# rampshh.net
KiCad netlist of a schematic drawn in Altium Designer
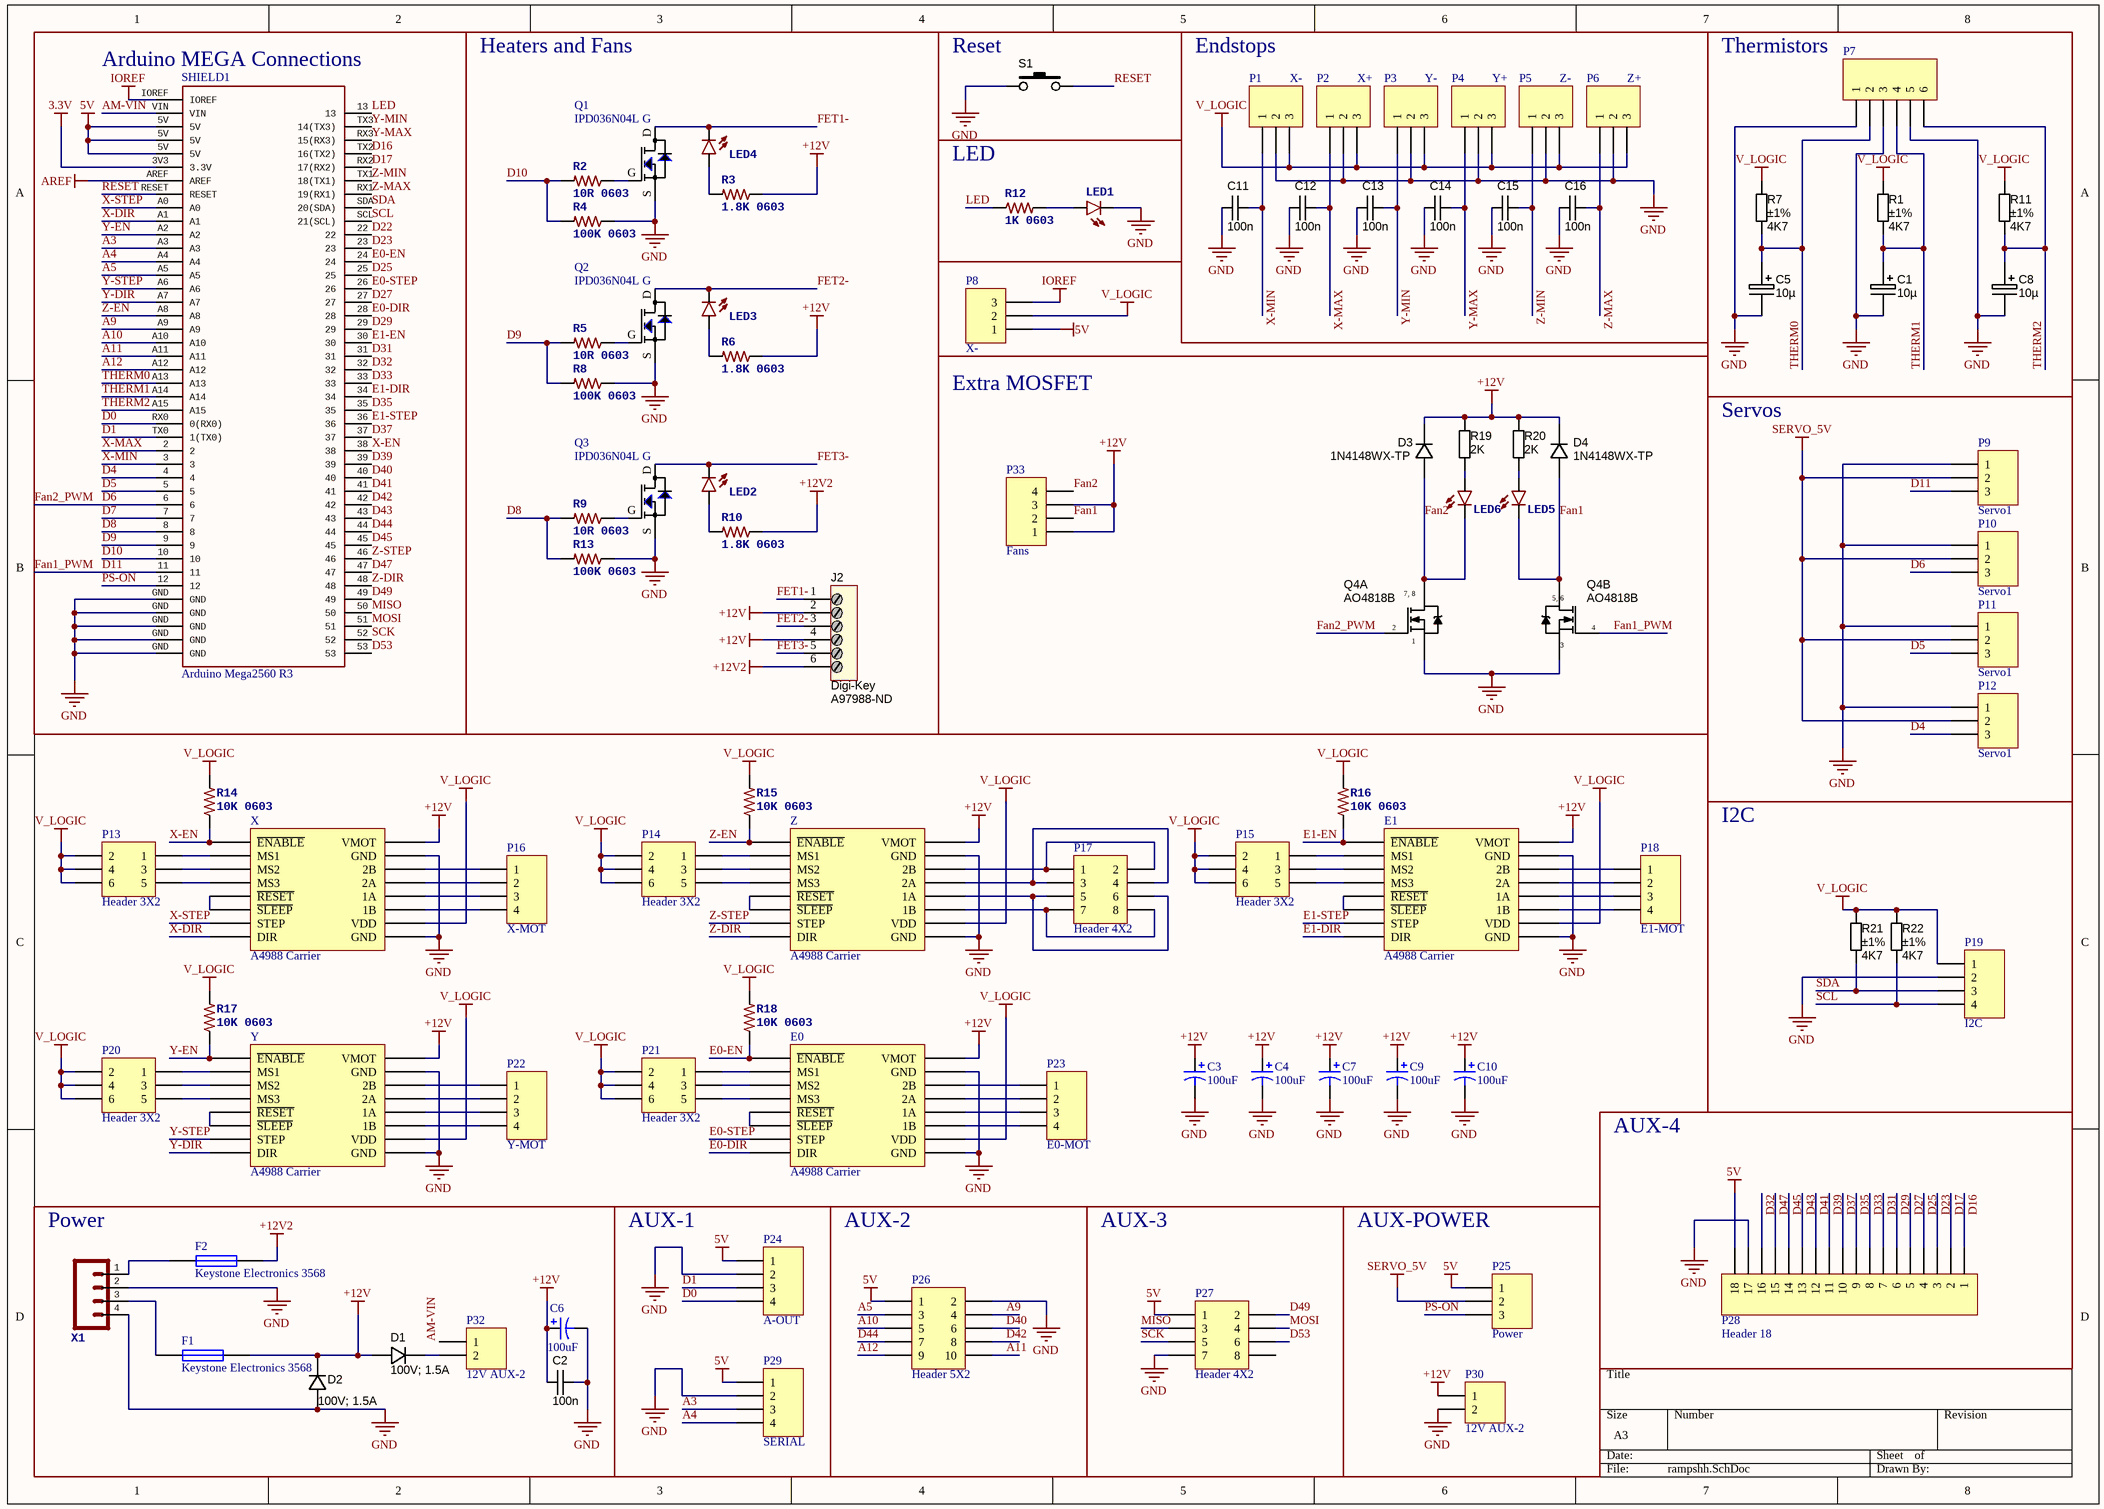
[diagram p0: rampshh.SchDoc]

(export (version "E")
  (design (tool "Eeschema 10.0.6"))
  (components
    (comp (ref "C1")
      (value "10µ")
      (footprint "153CLV-0405")
      (description "Capacitor SMD Electrolytic 10uF 20% 100V Radial")
      (fields (field (name "TOLERANCE") "±20%") (field (name "MANUFACTURER") "Panasonic - ECG"))
      (libsource (lib "PBL - Capacitors") (part "CAPE_10u_100V_SMD"))
    )
    (comp (ref "C2")
      (value "100n")
      (footprint "CAPC2012X135N")
      (description "Capacitor SMD Cer 100nF 10% 50V X7R 0805")
      (fields (field (name "TOLERANCE") "±10%") (field (name "Comment") "approved sub OK"))
      (libsource (lib "PBL - Capacitors") (part "CAPC_100n_0805_X7R_50V_10%"))
    )
    (comp (ref "C3")
      (value "100uF")
      (footprint "Kemet EDK107M035A9HAA")
      (description "Polarized Capacitor (Radial)")
      (fields (field (name "PUBLISHER") "Altium Limited"))
      (libsource (lib "Miscellaneous Devices") (part "Cap Pol1"))
    )
    (comp (ref "C4")
      (value "100uF")
      (footprint "Kemet EDK107M035A9HAA")
      (description "Polarized Capacitor (Radial)")
      (fields (field (name "PUBLISHER") "Altium Limited"))
      (libsource (lib "Miscellaneous Devices") (part "Cap Pol1"))
    )
    (comp (ref "C5")
      (value "10µ")
      (footprint "153CLV-0405")
      (description "Capacitor SMD Electrolytic 10uF 20% 100V Radial")
      (fields (field (name "TOLERANCE") "±20%") (field (name "MANUFACTURER") "Panasonic - ECG"))
      (libsource (lib "PBL - Capacitors") (part "CAPE_10u_100V_SMD"))
    )
    (comp (ref "C6")
      (value "100uF")
      (footprint "Kemet EDK107M035A9HAA")
      (description "Polarized Capacitor (Radial)")
      (fields (field (name "PUBLISHER") "Altium Limited"))
      (libsource (lib "Miscellaneous Devices") (part "Cap Pol1"))
    )
    (comp (ref "C7")
      (value "100uF")
      (footprint "Kemet EDK107M035A9HAA")
      (description "Polarized Capacitor (Radial)")
      (fields (field (name "PUBLISHER") "Altium Limited"))
      (libsource (lib "Miscellaneous Devices") (part "Cap Pol1"))
    )
    (comp (ref "C8")
      (value "10µ")
      (footprint "153CLV-0405")
      (description "Capacitor SMD Electrolytic 10uF 20% 100V Radial")
      (fields (field (name "TOLERANCE") "±20%") (field (name "MANUFACTURER") "Panasonic - ECG"))
      (libsource (lib "PBL - Capacitors") (part "CAPE_10u_100V_SMD"))
    )
    (comp (ref "C9")
      (value "100uF")
      (footprint "Kemet EDK107M035A9HAA")
      (description "Polarized Capacitor (Radial)")
      (fields (field (name "PUBLISHER") "Altium Limited"))
      (libsource (lib "Miscellaneous Devices") (part "Cap Pol1"))
    )
    (comp (ref "C10")
      (value "100uF")
      (footprint "Kemet EDK107M035A9HAA")
      (description "Polarized Capacitor (Radial)")
      (fields (field (name "PUBLISHER") "Altium Limited"))
      (libsource (lib "Miscellaneous Devices") (part "Cap Pol1"))
    )
    (comp (ref "C11")
      (value "100n")
      (footprint "CAPC1608X90N")
      (description "Capacitor SMD Cer 100nF 10% 50V X7R 0603")
      (fields (field (name "TOLERANCE") "±10%") (field (name "Comment") "approved sub OK"))
      (libsource (lib "PBL - Capacitors") (part "CAPC_100n_0603_X7R_50V_10%"))
    )
    (comp (ref "C12")
      (value "100n")
      (footprint "CAPC1608X90N")
      (description "Capacitor SMD Cer 100nF 10% 50V X7R 0603")
      (fields (field (name "TOLERANCE") "±10%") (field (name "Comment") "approved sub OK"))
      (libsource (lib "PBL - Capacitors") (part "CAPC_100n_0603_X7R_50V_10%"))
    )
    (comp (ref "C13")
      (value "100n")
      (footprint "CAPC1608X90N")
      (description "Capacitor SMD Cer 100nF 10% 50V X7R 0603")
      (fields (field (name "TOLERANCE") "±10%") (field (name "Comment") "approved sub OK"))
      (libsource (lib "PBL - Capacitors") (part "CAPC_100n_0603_X7R_50V_10%"))
    )
    (comp (ref "C14")
      (value "100n")
      (footprint "CAPC1608X90N")
      (description "Capacitor SMD Cer 100nF 10% 50V X7R 0603")
      (fields (field (name "TOLERANCE") "±10%") (field (name "Comment") "approved sub OK"))
      (libsource (lib "PBL - Capacitors") (part "CAPC_100n_0603_X7R_50V_10%"))
    )
    (comp (ref "C15")
      (value "100n")
      (footprint "CAPC1608X90N")
      (description "Capacitor SMD Cer 100nF 10% 50V X7R 0603")
      (fields (field (name "TOLERANCE") "±10%") (field (name "Comment") "approved sub OK"))
      (libsource (lib "PBL - Capacitors") (part "CAPC_100n_0603_X7R_50V_10%"))
    )
    (comp (ref "C16")
      (value "100n")
      (footprint "CAPC1608X90N")
      (description "Capacitor SMD Cer 100nF 10% 50V X7R 0603")
      (fields (field (name "TOLERANCE") "±10%") (field (name "Comment") "approved sub OK"))
      (libsource (lib "PBL - Capacitors") (part "CAPC_100n_0603_X7R_50V_10%"))
    )
    (comp (ref "D1")
      (value "100V; 1.5A")
      (footprint "DO-214AC")
      (description "Diode SMD 100V 1.5A SMA")
      (libsource (lib "PBL - Diodes") (part "DIODE_100V_1.5A_SMA"))
    )
    (comp (ref "D2")
      (value "100V; 1.5A")
      (footprint "DO-214AC")
      (description "Diode SMD 100V 1.5A SMA")
      (libsource (lib "PBL - Diodes") (part "DIODE_100V_1.5A_SMA"))
    )
    (comp (ref "D3")
      (value "DIODE_75V_500mW")
      (footprint "SOD323")
      (description "Diode SMD 300mA 0.5W SOD323")
      (fields
        (field (name "MANUFACTURER") "Micro Commercial Co")
        (field (name "MANUFACTURER PART NUMBER") "1N4148WX-TP")
      )
      (libsource (lib "PBL - Diodes") (part "DIODE_75V_500mW"))
    )
    (comp (ref "D4")
      (value "DIODE_75V_500mW")
      (footprint "SOD323")
      (description "Diode SMD 300mA 0.5W SOD323")
      (fields
        (field (name "MANUFACTURER") "Micro Commercial Co")
        (field (name "MANUFACTURER PART NUMBER") "1N4148WX-TP")
      )
      (libsource (lib "PBL - Diodes") (part "DIODE_75V_500mW"))
    )
    (comp (ref "E0")
      (value "A4988 Carrier")
      (footprint "A4988 Carrier")
      (libsource (lib "Schlib1") (part "A4988 Carrier"))
    )
    (comp (ref "E1")
      (value "A4988 Carrier")
      (footprint "A4988 Carrier")
      (libsource (lib "Schlib1") (part "A4988 Carrier"))
    )
    (comp (ref "F1")
      (value "Keystone Electronics 3568")
      (footprint "Keystone Electronics 3568 Fuse Holder")
      (description "Fuse")
      (fields (field (name "PUBLISHER") "Altium Limited"))
      (libsource (lib "Miscellaneous Devices") (part "Fuse 1"))
    )
    (comp (ref "F2")
      (value "Keystone Electronics 3568")
      (footprint "Keystone Electronics 3568 Fuse Holder")
      (description "Fuse")
      (fields (field (name "PUBLISHER") "Altium Limited"))
      (libsource (lib "Miscellaneous Devices") (part "Fuse 1"))
    )
    (comp (ref "J2")
      (value "6P_ScrewTerm_90S")
      (footprint "6P_PCB_ScrewTerm90S")
      (description "TERM BLOCK 6POS SIDE ENT STACKABLE 5.08MM")
      (fields
        (field (name "VOLTAGE") "300V")
        (field (name "SUPPLIER 1") "Digi-Key")
        (field (name "SUPPLIER PART NUMBER 1") "A97988-ND")
      )
      (libsource (lib "PBL - Connectors") (part "6P_ScrewTerm_90S"))
    )
    (comp (ref "LED1")
      (value "Blue LEDs for production use    Various blue LEDs stocked by SparkFun production 0603 - DIO-08575 Rebel - DIO-09553 1206 - DIO-09911")
      (footprint "LED-0603")
      (libsource (lib "SparkFun-LED") (part "LED-BLUE0603"))
    )
    (comp (ref "LED2")
      (value "Blue LEDs for production use    Various blue LEDs stocked by SparkFun production 0603 - DIO-08575 Rebel - DIO-09553 1206 - DIO-09911")
      (footprint "LED-0603")
      (libsource (lib "SparkFun-LED") (part "LED-BLUE0603"))
    )
    (comp (ref "LED3")
      (value "Blue LEDs for production use    Various blue LEDs stocked by SparkFun production 0603 - DIO-08575 Rebel - DIO-09553 1206 - DIO-09911")
      (footprint "LED-0603")
      (libsource (lib "SparkFun-LED") (part "LED-BLUE0603"))
    )
    (comp (ref "LED4")
      (value "Blue LEDs for production use    Various blue LEDs stocked by SparkFun production 0603 - DIO-08575 Rebel - DIO-09553 1206 - DIO-09911")
      (footprint "LED-0603")
      (libsource (lib "SparkFun-LED") (part "LED-BLUE0603"))
    )
    (comp (ref "LED5")
      (value "Blue LEDs for production use    Various blue LEDs stocked by SparkFun production 0603 - DIO-08575 Rebel - DIO-09553 1206 - DIO-09911")
      (footprint "LED-0603")
      (libsource (lib "SparkFun-LED") (part "LED-BLUE0603"))
    )
    (comp (ref "LED6")
      (value "Blue LEDs for production use    Various blue LEDs stocked by SparkFun production 0603 - DIO-08575 Rebel - DIO-09553 1206 - DIO-09911")
      (footprint "LED-0603")
      (libsource (lib "SparkFun-LED") (part "LED-BLUE0603"))
    )
    (comp (ref "P1")
      (value "X-")
      (footprint "Header 3x1 Male")
      (description "Header, 3-Pin")
      (fields (field (name "PUBLISHER") "Altium Limited"))
      (libsource (lib "Miscellaneous Connectors") (part "Header 3"))
    )
    (comp (ref "P2")
      (value "X+")
      (footprint "Header 3x1 Male")
      (description "Header, 3-Pin")
      (fields (field (name "PUBLISHER") "Altium Limited"))
      (libsource (lib "Miscellaneous Connectors") (part "Header 3"))
    )
    (comp (ref "P3")
      (value "Y-")
      (footprint "Header 3x1 Male")
      (description "Header, 3-Pin")
      (fields (field (name "PUBLISHER") "Altium Limited"))
      (libsource (lib "Miscellaneous Connectors") (part "Header 3"))
    )
    (comp (ref "P4")
      (value "Y+")
      (footprint "Header 3x1 Male")
      (description "Header, 3-Pin")
      (fields (field (name "PUBLISHER") "Altium Limited"))
      (libsource (lib "Miscellaneous Connectors") (part "Header 3"))
    )
    (comp (ref "P5")
      (value "Z-")
      (footprint "Header 3x1 Male")
      (description "Header, 3-Pin")
      (fields (field (name "PUBLISHER") "Altium Limited"))
      (libsource (lib "Miscellaneous Connectors") (part "Header 3"))
    )
    (comp (ref "P6")
      (value "Z+")
      (footprint "Header 3x1 Male")
      (description "Header, 3-Pin")
      (fields (field (name "PUBLISHER") "Altium Limited"))
      (libsource (lib "Miscellaneous Connectors") (part "Header 3"))
    )
    (comp (ref "P7")
      (value "Header 6")
      (footprint "HDR1X6")
      (description "Header, 6-Pin")
      (fields (field (name "PUBLISHER") "Altium Limited"))
      (libsource (lib "Miscellaneous Connectors") (part "Header 6"))
    )
    (comp (ref "P8")
      (value "X-")
      (footprint "Header 3x1 Male")
      (description "Header, 3-Pin")
      (fields (field (name "PUBLISHER") "Altium Limited"))
      (libsource (lib "") (part "Header 3_2"))
    )
    (comp (ref "P9")
      (value "Servo1")
      (footprint "Header 3x1 Male")
      (description "Header, 3-Pin")
      (fields (field (name "PUBLISHER") "Altium Limited"))
      (libsource (lib "") (part "Header 3_1"))
    )
    (comp (ref "P10")
      (value "Servo1")
      (footprint "Header 3x1 Male")
      (description "Header, 3-Pin")
      (fields (field (name "PUBLISHER") "Altium Limited"))
      (libsource (lib "") (part "Header 3_1"))
    )
    (comp (ref "P11")
      (value "Servo1")
      (footprint "Header 3x1 Male")
      (description "Header, 3-Pin")
      (fields (field (name "PUBLISHER") "Altium Limited"))
      (libsource (lib "") (part "Header 3_1"))
    )
    (comp (ref "P12")
      (value "Servo1")
      (footprint "Header 3x1 Male")
      (description "Header, 3-Pin")
      (fields (field (name "PUBLISHER") "Altium Limited"))
      (libsource (lib "") (part "Header 3_1"))
    )
    (comp (ref "P13")
      (value "Header 3X2")
      (footprint "Header 3x2 Male")
      (description "Header, 3-Pin, Dual row")
      (fields (field (name "PUBLISHER") "Altium Limited"))
      (libsource (lib "Miscellaneous Connectors") (part "Header 3X2"))
    )
    (comp (ref "P14")
      (value "Header 3X2")
      (footprint "Header 3x2 Male")
      (description "Header, 3-Pin, Dual row")
      (fields (field (name "PUBLISHER") "Altium Limited"))
      (libsource (lib "Miscellaneous Connectors") (part "Header 3X2"))
    )
    (comp (ref "P15")
      (value "Header 3X2")
      (footprint "Header 3x2 Male")
      (description "Header, 3-Pin, Dual row")
      (fields (field (name "PUBLISHER") "Altium Limited"))
      (libsource (lib "Miscellaneous Connectors") (part "Header 3X2"))
    )
    (comp (ref "P16")
      (value "X-MOT")
      (footprint "Header 4x1 Male")
      (description "Header, 4-Pin")
      (fields (field (name "PUBLISHER") "Altium Limited"))
      (libsource (lib "Miscellaneous Connectors") (part "Header 4"))
    )
    (comp (ref "P17")
      (value "Header 4X2")
      (footprint "Header 4x2 Male")
      (description "Header, 4-Pin, Dual row")
      (fields (field (name "PUBLISHER") "Altium Limited"))
      (libsource (lib "Miscellaneous Connectors") (part "Header 4X2"))
    )
    (comp (ref "P18")
      (value "E1-MOT")
      (footprint "Header 4x1 Male")
      (description "Header, 4-Pin")
      (fields (field (name "PUBLISHER") "Altium Limited"))
      (libsource (lib "Miscellaneous Connectors") (part "Header 4"))
    )
    (comp (ref "P19")
      (value "I2C")
      (footprint "Header 4x1 Male")
      (description "Header, 4-Pin")
      (fields (field (name "PUBLISHER") "Altium Limited"))
      (libsource (lib "Miscellaneous Connectors") (part "Header 4"))
    )
    (comp (ref "P20")
      (value "Header 3X2")
      (footprint "Header 3x2 Male")
      (description "Header, 3-Pin, Dual row")
      (fields (field (name "PUBLISHER") "Altium Limited"))
      (libsource (lib "Miscellaneous Connectors") (part "Header 3X2"))
    )
    (comp (ref "P21")
      (value "Header 3X2")
      (footprint "Header 3x2 Male")
      (description "Header, 3-Pin, Dual row")
      (fields (field (name "PUBLISHER") "Altium Limited"))
      (libsource (lib "Miscellaneous Connectors") (part "Header 3X2"))
    )
    (comp (ref "P22")
      (value "Y-MOT")
      (footprint "Header 4x1 Male")
      (description "Header, 4-Pin")
      (fields (field (name "PUBLISHER") "Altium Limited"))
      (libsource (lib "Miscellaneous Connectors") (part "Header 4"))
    )
    (comp (ref "P23")
      (value "E0-MOT")
      (footprint "Header 4x1 Male")
      (description "Header, 4-Pin")
      (fields (field (name "PUBLISHER") "Altium Limited"))
      (libsource (lib "Miscellaneous Connectors") (part "Header 4"))
    )
    (comp (ref "P24")
      (value "A-OUT")
      (footprint "Header 4x1 Male")
      (description "Header, 4-Pin")
      (fields (field (name "PUBLISHER") "Altium Limited"))
      (libsource (lib "Miscellaneous Connectors") (part "Header 4"))
    )
    (comp (ref "P25")
      (value "Power")
      (footprint "Header 3x1 Male")
      (description "Header, 3-Pin")
      (fields (field (name "PUBLISHER") "Altium Limited"))
      (libsource (lib "") (part "Header 3_1"))
    )
    (comp (ref "P26")
      (value "Header 5X2")
      (footprint "Header 5x2 Male")
      (description "Header, 5-Pin, Dual row")
      (fields (field (name "PUBLISHER") "Altium Limited"))
      (libsource (lib "Miscellaneous Connectors") (part "Header 5X2"))
    )
    (comp (ref "P27")
      (value "Header 4X2")
      (footprint "Header 4x2 Male")
      (description "Header, 4-Pin, Dual row")
      (fields (field (name "PUBLISHER") "Altium Limited"))
      (libsource (lib "Miscellaneous Connectors") (part "Header 4X2"))
    )
    (comp (ref "P28")
      (value "Header 18")
      (footprint "HDR1X18")
      (description "Header, 18-Pin")
      (fields (field (name "PUBLISHER") "Altium Limited"))
      (libsource (lib "Miscellaneous Connectors") (part "Header 18"))
    )
    (comp (ref "P29")
      (value "SERIAL")
      (footprint "Header 4x1 Male")
      (description "Header, 4-Pin")
      (fields (field (name "PUBLISHER") "Altium Limited"))
      (libsource (lib "Miscellaneous Connectors") (part "Header 4"))
    )
    (comp (ref "P30")
      (value "12V AUX-2")
      (footprint "Header 2x1 Male")
      (description "Header, 2-Pin")
      (fields (field (name "PUBLISHER") "Altium Limited"))
      (libsource (lib "Miscellaneous Connectors") (part "Header 2"))
    )
    (comp (ref "P32")
      (value "12V AUX-2")
      (footprint "Header 2x1 Male")
      (description "Header, 2-Pin")
      (fields (field (name "PUBLISHER") "Altium Limited"))
      (libsource (lib "Miscellaneous Connectors") (part "Header 2"))
    )
    (comp (ref "P33")
      (value "Fans")
      (footprint "Header 4x1 Male")
      (description "Header, 4-Pin")
      (fields (field (name "PUBLISHER") "Altium Limited"))
      (libsource (lib "") (part "Header 4_1"))
    )
    (comp (ref "Q1")
      (value "IPD036N04L G")
      (footprint "IPD036N04L G")
      (libsource (lib "Schlib1") (part "IPD036N04L G"))
    )
    (comp (ref "Q2")
      (value "IPD036N04L G")
      (footprint "IPD036N04L G")
      (libsource (lib "Schlib1") (part "IPD036N04L G"))
    )
    (comp (ref "Q3")
      (value "IPD036N04L G")
      (footprint "IPD036N04L G")
      (libsource (lib "Schlib1") (part "IPD036N04L G"))
    )
    (comp (ref "Q4")
      (value "MOSFET_AO4818B")
      (footprint "SOIC127P600X175-8AN")
      (description "MOSFET Dual-Channel 30V 8.5A SOIC-8 SMD")
      (fields (field (name "MANUFACTURER PART NUMBER 1") "AO4818B"))
      (libsource (lib "PBL - Transistors") (part "MOSFET_AO4818B"))
    )
    (comp (ref "R1")
      (value "4K7")
      (footprint "RESC2012X70N")
      (description "Resistor SMD chip 4.7k Ohm 0.125W 1% 0805")
      (fields (field (name "TOLERANCE") "±1%") (field (name "Comment") "Thick Film"))
      (libsource (lib "PBL - Resistors") (part "RES_4K7_0805_1%"))
    )
    (comp (ref "R2")
      (value "10R 0603")
      (footprint "RESC1608X55N")
      (libsource (lib "SparkFun-Resistors") (part "1KOHM-1/10W-1%(0603)"))
    )
    (comp (ref "R3")
      (value "1.8K 0603")
      (footprint "0603-RES")
      (libsource (lib "SparkFun-Resistors") (part "1KOHM-1/10W-1%(0603)"))
    )
    (comp (ref "R4")
      (value "100K 0603")
      (footprint "RESC1608X55N")
      (libsource (lib "SparkFun-Resistors") (part "1KOHM-1/10W-1%(0603)"))
    )
    (comp (ref "R5")
      (value "10R 0603")
      (footprint "RESC1608X55N")
      (libsource (lib "SparkFun-Resistors") (part "1KOHM-1/10W-1%(0603)"))
    )
    (comp (ref "R6")
      (value "1.8K 0603")
      (footprint "0603-RES")
      (libsource (lib "SparkFun-Resistors") (part "1KOHM-1/10W-1%(0603)"))
    )
    (comp (ref "R7")
      (value "4K7")
      (footprint "RESC2012X70N")
      (description "Resistor SMD chip 4.7k Ohm 0.125W 1% 0805")
      (fields (field (name "TOLERANCE") "±1%") (field (name "Comment") "Thick Film"))
      (libsource (lib "PBL - Resistors") (part "RES_4K7_0805_1%"))
    )
    (comp (ref "R8")
      (value "100K 0603")
      (footprint "RESC1608X55N")
      (libsource (lib "SparkFun-Resistors") (part "1KOHM-1/10W-1%(0603)"))
    )
    (comp (ref "R9")
      (value "10R 0603")
      (footprint "RESC1608X55N")
      (libsource (lib "SparkFun-Resistors") (part "1KOHM-1/10W-1%(0603)"))
    )
    (comp (ref "R10")
      (value "1.8K 0603")
      (footprint "0603-RES")
      (libsource (lib "SparkFun-Resistors") (part "1KOHM-1/10W-1%(0603)"))
    )
    (comp (ref "R11")
      (value "4K7")
      (footprint "RESC2012X70N")
      (description "Resistor SMD chip 4.7k Ohm 0.125W 1% 0805")
      (fields (field (name "TOLERANCE") "±1%") (field (name "Comment") "Thick Film"))
      (libsource (lib "PBL - Resistors") (part "RES_4K7_0805_1%"))
    )
    (comp (ref "R12")
      (value "1K 0603")
      (footprint "0603-RES")
      (libsource (lib "SparkFun-Resistors") (part "1KOHM-1/10W-1%(0603)"))
    )
    (comp (ref "R13")
      (value "100K 0603")
      (footprint "RESC1608X55N")
      (libsource (lib "SparkFun-Resistors") (part "1KOHM-1/10W-1%(0603)"))
    )
    (comp (ref "R14")
      (value "10K 0603")
      (footprint "0603-RES")
      (libsource (lib "SparkFun-Resistors") (part "1KOHM-1/10W-1%(0603)"))
    )
    (comp (ref "R15")
      (value "10K 0603")
      (footprint "0603-RES")
      (libsource (lib "SparkFun-Resistors") (part "1KOHM-1/10W-1%(0603)"))
    )
    (comp (ref "R16")
      (value "10K 0603")
      (footprint "0603-RES")
      (libsource (lib "SparkFun-Resistors") (part "1KOHM-1/10W-1%(0603)"))
    )
    (comp (ref "R17")
      (value "10K 0603")
      (footprint "0603-RES")
      (libsource (lib "SparkFun-Resistors") (part "1KOHM-1/10W-1%(0603)"))
    )
    (comp (ref "R18")
      (value "10K 0603")
      (footprint "0603-RES")
      (libsource (lib "SparkFun-Resistors") (part "1KOHM-1/10W-1%(0603)"))
    )
    (comp (ref "R19")
      (value "2K")
      (footprint "RESC1608X55N")
      (description "Resistor SMD chip 330 Ohm 0.1W 5% 0603")
      (fields (field (name "TOLERANCE") "±5%") (field (name "Comment") "Thick Film"))
      (libsource (lib "PBL - Resistors") (part "RES_330R_0603_5%"))
    )
    (comp (ref "R20")
      (value "2K")
      (footprint "RESC1608X55N")
      (description "Resistor SMD chip 330 Ohm 0.1W 5% 0603")
      (fields (field (name "TOLERANCE") "±5%") (field (name "Comment") "Thick Film"))
      (libsource (lib "PBL - Resistors") (part "RES_330R_0603_5%"))
    )
    (comp (ref "R21")
      (value "4K7")
      (footprint "RESC2012X70N")
      (description "Resistor SMD chip 4.7k Ohm 0.125W 1% 0805")
      (fields (field (name "TOLERANCE") "±1%") (field (name "Comment") "Thick Film"))
      (libsource (lib "PBL - Resistors") (part "RES_4K7_0805_1%"))
    )
    (comp (ref "R22")
      (value "4K7")
      (footprint "RESC2012X70N")
      (description "Resistor SMD chip 4.7k Ohm 0.125W 1% 0805")
      (fields (field (name "TOLERANCE") "±1%") (field (name "Comment") "Thick Film"))
      (libsource (lib "PBL - Resistors") (part "RES_4K7_0805_1%"))
    )
    (comp (ref "S1")
      (value "SW_THT_PB_4.3mm")
      (footprint "FSMRACD")
      (description "Switch, tact, 4.3mm stem")
      (libsource (lib "PBL - Switches") (part "SW_THT_PB_4.3mm"))
    )
    (comp (ref "SHIELD1")
      (value "Arduino Mega2560 R3")
      (footprint "Arduino Mega Shield - No Text")
      (libsource (lib "Schlib1") (part "Arduino Mega2560 R3"))
    )
    (comp (ref "X")
      (value "A4988 Carrier")
      (footprint "A4988 Carrier")
      (libsource (lib "Schlib1") (part "A4988 Carrier"))
    )
    (comp (ref "X1")
      (value "Header 4Standard 4-pin 0.1\" header. Use with straight break away headers (SKU : PRT-00116), right angle break away headers (PRT-00553), swiss pins (PRT-00743), machine pins (PRT-00117), and female headers (PRT-00115). Molex polarized connector foot print use with SKU : PRT-08231 with associated crimp pins and housings. 1MM SMD Version SKU: PRT-10208")
      (footprint "MSTBA4")
      (libsource (lib "SparkFun-Connectors") (part "M04SCREW"))
    )
    (comp (ref "Y")
      (value "A4988 Carrier")
      (footprint "A4988 Carrier")
      (libsource (lib "Schlib1") (part "A4988 Carrier"))
    )
    (comp (ref "Z")
      (value "A4988 Carrier")
      (footprint "A4988 Carrier")
      (libsource (lib "Schlib1") (part "A4988 Carrier"))
    )
  )
  (nets
    (net (code "1") (name "+12V") (class "Default")
      (node (ref "C10") (pin "1") (pinfunction "1_1") (pintype "passive"))
      (node (ref "C2") (pin "1") (pintype "passive"))
      (node (ref "C3") (pin "1") (pinfunction "1_1") (pintype "passive"))
      (node (ref "C4") (pin "1") (pinfunction "1_1") (pintype "passive"))
      (node (ref "C6") (pin "1") (pinfunction "1_1") (pintype "passive"))
      (node (ref "C7") (pin "1") (pinfunction "1_1") (pintype "passive"))
      (node (ref "C9") (pin "1") (pinfunction "1_1") (pintype "passive"))
      (node (ref "D1") (pin "A") (pinfunction "A_A") (pintype "passive"))
      (node (ref "D2") (pin "K") (pinfunction "K_K") (pintype "passive"))
      (node (ref "D3") (pin "K") (pinfunction "K_K") (pintype "passive"))
      (node (ref "D4") (pin "K") (pinfunction "K_K") (pintype "passive"))
      (node (ref "E0") (pin "VMOT") (pinfunction "VMOT_VMOT") (pintype "passive"))
      (node (ref "E1") (pin "VMOT") (pinfunction "VMOT_VMOT") (pintype "passive"))
      (node (ref "F1") (pin "2") (pinfunction "2_2") (pintype "passive"))
      (node (ref "J2") (pin "2") (pinfunction "2_2") (pintype "passive"))
      (node (ref "J2") (pin "4") (pinfunction "4_4") (pintype "passive"))
      (node (ref "P30") (pin "1") (pinfunction "1_1") (pintype "passive"))
      (node (ref "P33") (pin "1") (pinfunction "1_1") (pintype "passive"))
      (node (ref "P33") (pin "3") (pinfunction "3_3") (pintype "passive"))
      (node (ref "R19") (pin "1") (pinfunction "1_1") (pintype "passive"))
      (node (ref "R20") (pin "1") (pinfunction "1_1") (pintype "passive"))
      (node (ref "R3") (pin "1") (pinfunction "1_1") (pintype "passive"))
      (node (ref "R6") (pin "1") (pinfunction "1_1") (pintype "passive"))
      (node (ref "X") (pin "VMOT") (pinfunction "VMOT_VMOT") (pintype "passive"))
      (node (ref "Y") (pin "VMOT") (pinfunction "VMOT_VMOT") (pintype "passive"))
      (node (ref "Z") (pin "VMOT") (pinfunction "VMOT_VMOT") (pintype "passive"))
    )
    (net (code "2") (name "+12V2") (class "Default")
      (node (ref "F2") (pin "2") (pinfunction "2_2") (pintype "passive"))
      (node (ref "J2") (pin "6") (pinfunction "6_6") (pintype "passive"))
      (node (ref "R10") (pin "1") (pinfunction "1_1") (pintype "passive"))
    )
    (net (code "3") (name "/A3") (class "Default")
      (node (ref "P29") (pin "3") (pinfunction "3_3") (pintype "passive"))
      (node (ref "SHIELD1") (pin "A3") (pinfunction "A3_A3") (pintype "passive"))
    )
    (net (code "4") (name "/A4") (class "Default")
      (node (ref "P29") (pin "4") (pinfunction "4_4") (pintype "passive"))
      (node (ref "SHIELD1") (pin "A4") (pinfunction "A4_A4") (pintype "passive"))
    )
    (net (code "5") (name "/A5") (class "Default")
      (node (ref "P26") (pin "3") (pinfunction "3_3") (pintype "passive"))
      (node (ref "SHIELD1") (pin "A5") (pinfunction "A5_A5") (pintype "passive"))
    )
    (net (code "6") (name "/A9") (class "Default")
      (node (ref "P26") (pin "4") (pinfunction "4_4") (pintype "passive"))
      (node (ref "SHIELD1") (pin "A9") (pinfunction "A9_A9") (pintype "passive"))
    )
    (net (code "7") (name "/A10") (class "Default")
      (node (ref "P26") (pin "5") (pinfunction "5_5") (pintype "passive"))
      (node (ref "SHIELD1") (pin "A10") (pinfunction "A10_A10") (pintype "passive"))
    )
    (net (code "8") (name "/A11") (class "Default")
      (node (ref "P26") (pin "10") (pinfunction "10_10") (pintype "passive"))
      (node (ref "SHIELD1") (pin "A11") (pinfunction "A11_A11") (pintype "passive"))
    )
    (net (code "9") (name "/A12") (class "Default")
      (node (ref "P26") (pin "9") (pinfunction "9_9") (pintype "passive"))
      (node (ref "SHIELD1") (pin "A12") (pinfunction "A12_A12") (pintype "passive"))
    )
    (net (code "10") (name "/AM-VIN") (class "Default")
      (node (ref "P32") (pin "1") (pinfunction "1_1") (pintype "passive"))
      (node (ref "SHIELD1") (pin "VIN") (pinfunction "VIN_VIN") (pintype "passive"))
    )
    (net (code "11") (name "/D0") (class "Default")
      (node (ref "P24") (pin "4") (pinfunction "4_4") (pintype "passive"))
      (node (ref "SHIELD1") (pin "RX0") (pinfunction "0(RX0)_RX0") (pintype "passive"))
    )
    (net (code "12") (name "/D1") (class "Default")
      (node (ref "P24") (pin "3") (pinfunction "3_3") (pintype "passive"))
      (node (ref "SHIELD1") (pin "TX0") (pinfunction "1(TX0)_TX0") (pintype "passive"))
    )
    (net (code "13") (name "/D4") (class "Default")
      (node (ref "P12") (pin "3") (pinfunction "3_3") (pintype "passive"))
      (node (ref "SHIELD1") (pin "4") (pinfunction "4_4") (pintype "passive"))
    )
    (net (code "14") (name "/D5") (class "Default")
      (node (ref "P11") (pin "3") (pinfunction "3_3") (pintype "passive"))
      (node (ref "SHIELD1") (pin "5") (pinfunction "5_5") (pintype "passive"))
    )
    (net (code "15") (name "/D6") (class "Default")
      (node (ref "P10") (pin "3") (pinfunction "3_3") (pintype "passive"))
      (node (ref "Q4") (pin "2") (pinfunction "G_2") (pintype "passive"))
      (node (ref "SHIELD1") (pin "6") (pinfunction "6_6") (pintype "passive"))
    )
    (net (code "16") (name "/D7") (class "Default")
      (node (ref "SHIELD1") (pin "7") (pinfunction "7_7") (pintype "passive"))
    )
    (net (code "17") (name "/D8") (class "Default")
      (node (ref "R13") (pin "2") (pinfunction "2_2") (pintype "passive"))
      (node (ref "R9") (pin "2") (pinfunction "2_2") (pintype "passive"))
      (node (ref "SHIELD1") (pin "8") (pinfunction "8_8") (pintype "passive"))
    )
    (net (code "18") (name "/D9") (class "Default")
      (node (ref "R5") (pin "2") (pinfunction "2_2") (pintype "passive"))
      (node (ref "R8") (pin "2") (pinfunction "2_2") (pintype "passive"))
      (node (ref "SHIELD1") (pin "9") (pinfunction "9_9") (pintype "passive"))
    )
    (net (code "19") (name "/D10") (class "Default")
      (node (ref "R2") (pin "2") (pinfunction "2_2") (pintype "passive"))
      (node (ref "R4") (pin "2") (pinfunction "2_2") (pintype "passive"))
      (node (ref "SHIELD1") (pin "10") (pinfunction "10_10") (pintype "passive"))
    )
    (net (code "20") (name "/D11") (class "Default")
      (node (ref "P9") (pin "3") (pinfunction "3_3") (pintype "passive"))
      (node (ref "Q4") (pin "4") (pinfunction "G_4") (pintype "passive"))
      (node (ref "SHIELD1") (pin "11") (pinfunction "11_11") (pintype "passive"))
    )
    (net (code "21") (name "/D16") (class "Default")
      (node (ref "P28") (pin "1") (pinfunction "1_1") (pintype "passive"))
      (node (ref "SHIELD1") (pin "TX2") (pinfunction "16(TX2)_TX2") (pintype "passive"))
    )
    (net (code "22") (name "/D17") (class "Default")
      (node (ref "P28") (pin "2") (pinfunction "2_2") (pintype "passive"))
      (node (ref "SHIELD1") (pin "RX2") (pinfunction "17(RX2)_RX2") (pintype "passive"))
    )
    (net (code "23") (name "/D22") (class "Default")
      (node (ref "SHIELD1") (pin "22") (pinfunction "22_22") (pintype "passive"))
    )
    (net (code "24") (name "/D23") (class "Default")
      (node (ref "P28") (pin "3") (pinfunction "3_3") (pintype "passive"))
      (node (ref "SHIELD1") (pin "23") (pinfunction "23_23") (pintype "passive"))
    )
    (net (code "25") (name "/D25") (class "Default")
      (node (ref "P28") (pin "4") (pinfunction "4_4") (pintype "passive"))
      (node (ref "SHIELD1") (pin "25") (pinfunction "25_25") (pintype "passive"))
    )
    (net (code "26") (name "/D27") (class "Default")
      (node (ref "P28") (pin "5") (pinfunction "5_5") (pintype "passive"))
      (node (ref "SHIELD1") (pin "27") (pinfunction "27_27") (pintype "passive"))
    )
    (net (code "27") (name "/D29") (class "Default")
      (node (ref "P28") (pin "6") (pinfunction "6_6") (pintype "passive"))
      (node (ref "SHIELD1") (pin "29") (pinfunction "29_29") (pintype "passive"))
    )
    (net (code "28") (name "/D31") (class "Default")
      (node (ref "P28") (pin "7") (pinfunction "7_7") (pintype "passive"))
      (node (ref "SHIELD1") (pin "31") (pinfunction "31_31") (pintype "passive"))
    )
    (net (code "29") (name "/D32") (class "Default")
      (node (ref "P28") (pin "16") (pinfunction "16_16") (pintype "passive"))
      (node (ref "SHIELD1") (pin "32") (pinfunction "32_32") (pintype "passive"))
    )
    (net (code "30") (name "/D33") (class "Default")
      (node (ref "P28") (pin "8") (pinfunction "8_8") (pintype "passive"))
      (node (ref "SHIELD1") (pin "33") (pinfunction "33_33") (pintype "passive"))
    )
    (net (code "31") (name "/D35") (class "Default")
      (node (ref "P28") (pin "9") (pinfunction "9_9") (pintype "passive"))
      (node (ref "SHIELD1") (pin "35") (pinfunction "35_35") (pintype "passive"))
    )
    (net (code "32") (name "/D37") (class "Default")
      (node (ref "P28") (pin "10") (pinfunction "10_10") (pintype "passive"))
      (node (ref "SHIELD1") (pin "37") (pinfunction "37_37") (pintype "passive"))
    )
    (net (code "33") (name "/D39") (class "Default")
      (node (ref "P28") (pin "11") (pinfunction "11_11") (pintype "passive"))
      (node (ref "SHIELD1") (pin "39") (pinfunction "39_39") (pintype "passive"))
    )
    (net (code "34") (name "/D40") (class "Default")
      (node (ref "P26") (pin "6") (pinfunction "6_6") (pintype "passive"))
      (node (ref "SHIELD1") (pin "40") (pinfunction "40_40") (pintype "passive"))
    )
    (net (code "35") (name "/D41") (class "Default")
      (node (ref "P28") (pin "12") (pinfunction "12_12") (pintype "passive"))
      (node (ref "SHIELD1") (pin "41") (pinfunction "41_41") (pintype "passive"))
    )
    (net (code "36") (name "/D42") (class "Default")
      (node (ref "P26") (pin "8") (pinfunction "8_8") (pintype "passive"))
      (node (ref "SHIELD1") (pin "42") (pinfunction "42_42") (pintype "passive"))
    )
    (net (code "37") (name "/D43") (class "Default")
      (node (ref "P28") (pin "13") (pinfunction "13_13") (pintype "passive"))
      (node (ref "SHIELD1") (pin "43") (pinfunction "43_43") (pintype "passive"))
    )
    (net (code "38") (name "/D44") (class "Default")
      (node (ref "P26") (pin "7") (pinfunction "7_7") (pintype "passive"))
      (node (ref "SHIELD1") (pin "44") (pinfunction "44_44") (pintype "passive"))
    )
    (net (code "39") (name "/D45") (class "Default")
      (node (ref "P28") (pin "14") (pinfunction "14_14") (pintype "passive"))
      (node (ref "SHIELD1") (pin "45") (pinfunction "45_45") (pintype "passive"))
    )
    (net (code "40") (name "/D47") (class "Default")
      (node (ref "P28") (pin "15") (pinfunction "15_15") (pintype "passive"))
      (node (ref "SHIELD1") (pin "47") (pinfunction "47_47") (pintype "passive"))
    )
    (net (code "41") (name "/D49") (class "Default")
      (node (ref "P27") (pin "2") (pinfunction "2_2") (pintype "passive"))
      (node (ref "SHIELD1") (pin "49") (pinfunction "49_49") (pintype "passive"))
    )
    (net (code "42") (name "/D53") (class "Default")
      (node (ref "P27") (pin "6") (pinfunction "6_6") (pintype "passive"))
      (node (ref "SHIELD1") (pin "53") (pinfunction "53_53") (pintype "passive"))
    )
    (net (code "43") (name "/E0-DIR") (class "Default")
      (node (ref "E0") (pin "DIR") (pinfunction "DIR_DIR") (pintype "passive"))
      (node (ref "SHIELD1") (pin "28") (pinfunction "28_28") (pintype "passive"))
    )
    (net (code "44") (name "/E0-EN") (class "Default")
      (node (ref "E0") (pin "ENABLE") (pinfunction "~{ENABLE}_ENABLE") (pintype "passive"))
      (node (ref "R18") (pin "1") (pinfunction "1_1") (pintype "passive"))
      (node (ref "SHIELD1") (pin "24") (pinfunction "24_24") (pintype "passive"))
    )
    (net (code "45") (name "/E0-STEP") (class "Default")
      (node (ref "E0") (pin "STEP") (pinfunction "STEP_STEP") (pintype "passive"))
      (node (ref "SHIELD1") (pin "26") (pinfunction "26_26") (pintype "passive"))
    )
    (net (code "46") (name "/E1-DIR") (class "Default")
      (node (ref "E1") (pin "DIR") (pinfunction "DIR_DIR") (pintype "passive"))
      (node (ref "SHIELD1") (pin "34") (pinfunction "34_34") (pintype "passive"))
    )
    (net (code "47") (name "/E1-EN") (class "Default")
      (node (ref "E1") (pin "ENABLE") (pinfunction "~{ENABLE}_ENABLE") (pintype "passive"))
      (node (ref "R16") (pin "1") (pinfunction "1_1") (pintype "passive"))
      (node (ref "SHIELD1") (pin "30") (pinfunction "30_30") (pintype "passive"))
    )
    (net (code "48") (name "/E1-STEP") (class "Default")
      (node (ref "E1") (pin "STEP") (pinfunction "STEP_STEP") (pintype "passive"))
      (node (ref "SHIELD1") (pin "36") (pinfunction "36_36") (pintype "passive"))
    )
    (net (code "49") (name "/FET1-") (class "Default")
      (node (ref "J2") (pin "1") (pinfunction "1_1") (pintype "passive"))
      (node (ref "LED4") (pin "C") (pinfunction "C_C") (pintype "passive"))
      (node (ref "Q1") (pin "D") (pinfunction "D_D") (pintype "passive"))
    )
    (net (code "50") (name "/FET2-") (class "Default")
      (node (ref "J2") (pin "3") (pinfunction "3_3") (pintype "passive"))
      (node (ref "LED3") (pin "C") (pinfunction "C_C") (pintype "passive"))
      (node (ref "Q2") (pin "D") (pinfunction "D_D") (pintype "passive"))
    )
    (net (code "51") (name "/FET3-") (class "Default")
      (node (ref "J2") (pin "5") (pinfunction "5_5") (pintype "passive"))
      (node (ref "LED2") (pin "C") (pinfunction "C_C") (pintype "passive"))
      (node (ref "Q3") (pin "D") (pinfunction "D_D") (pintype "passive"))
    )
    (net (code "52") (name "/Fan1") (class "Default")
      (node (ref "D4") (pin "A") (pinfunction "A_A") (pintype "passive"))
      (node (ref "LED5") (pin "C") (pinfunction "C_C") (pintype "passive"))
      (node (ref "P33") (pin "2") (pinfunction "2_2") (pintype "passive"))
      (node (ref "Q4") (pin "5") (pinfunction "D_5") (pintype "passive"))
      (node (ref "Q4") (pin "6") (pinfunction "D_6") (pintype "passive"))
    )
    (net (code "53") (name "/Fan2") (class "Default")
      (node (ref "D3") (pin "A") (pinfunction "A_A") (pintype "passive"))
      (node (ref "LED6") (pin "C") (pinfunction "C_C") (pintype "passive"))
      (node (ref "P33") (pin "4") (pinfunction "4_4") (pintype "passive"))
      (node (ref "Q4") (pin "7") (pinfunction "D_7") (pintype "passive"))
      (node (ref "Q4") (pin "8") (pinfunction "D_8") (pintype "passive"))
    )
    (net (code "54") (name "/LED") (class "Default")
      (node (ref "R12") (pin "1") (pinfunction "1_1") (pintype "passive"))
      (node (ref "SHIELD1") (pin "13") (pinfunction "13_13") (pintype "passive"))
    )
    (net (code "55") (name "/MISO") (class "Default")
      (node (ref "P27") (pin "3") (pinfunction "3_3") (pintype "passive"))
      (node (ref "SHIELD1") (pin "50") (pinfunction "50_50") (pintype "passive"))
    )
    (net (code "56") (name "/MOSI") (class "Default")
      (node (ref "P27") (pin "4") (pinfunction "4_4") (pintype "passive"))
      (node (ref "SHIELD1") (pin "51") (pinfunction "51_51") (pintype "passive"))
    )
    (net (code "57") (name "/PS-ON") (class "Default")
      (node (ref "P25") (pin "3") (pinfunction "3_3") (pintype "passive"))
      (node (ref "SHIELD1") (pin "12") (pinfunction "12_12") (pintype "passive"))
    )
    (net (code "58") (name "/RESET") (class "Default")
      (node (ref "S1") (pin "2") (pintype "passive"))
      (node (ref "SHIELD1") (pin "RESET") (pinfunction "RESET_RESET") (pintype "passive"))
    )
    (net (code "59") (name "/SCK") (class "Default")
      (node (ref "P27") (pin "5") (pinfunction "5_5") (pintype "passive"))
      (node (ref "SHIELD1") (pin "52") (pinfunction "52_52") (pintype "passive"))
    )
    (net (code "60") (name "/SCL") (class "Default")
      (node (ref "P19") (pin "4") (pinfunction "4_4") (pintype "passive"))
      (node (ref "R22") (pin "2") (pinfunction "2_2") (pintype "passive"))
      (node (ref "SHIELD1") (pin "SCL") (pinfunction "21(SCL)_SCL") (pintype "passive"))
    )
    (net (code "61") (name "/SDA") (class "Default")
      (node (ref "P19") (pin "3") (pinfunction "3_3") (pintype "passive"))
      (node (ref "R21") (pin "2") (pinfunction "2_2") (pintype "passive"))
      (node (ref "SHIELD1") (pin "SDA") (pinfunction "20(SDA)_SDA") (pintype "passive"))
    )
    (net (code "62") (name "/THERM0") (class "Default")
      (node (ref "C5") (pin "+") (pintype "passive"))
      (node (ref "P7") (pin "2") (pinfunction "2_2") (pintype "passive"))
      (node (ref "R7") (pin "2") (pinfunction "2_2") (pintype "passive"))
      (node (ref "SHIELD1") (pin "A13") (pinfunction "A13_A13") (pintype "passive"))
    )
    (net (code "63") (name "/THERM1") (class "Default")
      (node (ref "C1") (pin "+") (pintype "passive"))
      (node (ref "P7") (pin "4") (pinfunction "4_4") (pintype "passive"))
      (node (ref "R1") (pin "2") (pinfunction "2_2") (pintype "passive"))
      (node (ref "SHIELD1") (pin "A14") (pinfunction "A14_A14") (pintype "passive"))
    )
    (net (code "64") (name "/THERM2") (class "Default")
      (node (ref "C8") (pin "+") (pintype "passive"))
      (node (ref "P7") (pin "6") (pinfunction "6_6") (pintype "passive"))
      (node (ref "R11") (pin "2") (pinfunction "2_2") (pintype "passive"))
      (node (ref "SHIELD1") (pin "A15") (pinfunction "A15_A15") (pintype "passive"))
    )
    (net (code "65") (name "/X-DIR") (class "Default")
      (node (ref "SHIELD1") (pin "A1") (pinfunction "A1_A1") (pintype "passive"))
      (node (ref "X") (pin "DIR") (pinfunction "DIR_DIR") (pintype "passive"))
    )
    (net (code "66") (name "/X-EN") (class "Default")
      (node (ref "R14") (pin "1") (pinfunction "1_1") (pintype "passive"))
      (node (ref "SHIELD1") (pin "38") (pinfunction "38_38") (pintype "passive"))
      (node (ref "X") (pin "ENABLE") (pinfunction "~{ENABLE}_ENABLE") (pintype "passive"))
    )
    (net (code "67") (name "/X-MAX") (class "Default")
      (node (ref "C12") (pin "2") (pintype "passive"))
      (node (ref "P2") (pin "1") (pinfunction "1_1") (pintype "passive"))
      (node (ref "SHIELD1") (pin "2") (pinfunction "2_2") (pintype "passive"))
    )
    (net (code "68") (name "/X-MIN") (class "Default")
      (node (ref "C11") (pin "2") (pintype "passive"))
      (node (ref "P1") (pin "1") (pinfunction "1_1") (pintype "passive"))
      (node (ref "SHIELD1") (pin "3") (pinfunction "3_3") (pintype "passive"))
    )
    (net (code "69") (name "/X-STEP") (class "Default")
      (node (ref "SHIELD1") (pin "A0") (pinfunction "A0_A0") (pintype "passive"))
      (node (ref "X") (pin "STEP") (pinfunction "STEP_STEP") (pintype "passive"))
    )
    (net (code "70") (name "/Y-DIR") (class "Default")
      (node (ref "SHIELD1") (pin "A7") (pinfunction "A7_A7") (pintype "passive"))
      (node (ref "Y") (pin "DIR") (pinfunction "DIR_DIR") (pintype "passive"))
    )
    (net (code "71") (name "/Y-EN") (class "Default")
      (node (ref "R17") (pin "1") (pinfunction "1_1") (pintype "passive"))
      (node (ref "SHIELD1") (pin "A2") (pinfunction "A2_A2") (pintype "passive"))
      (node (ref "Y") (pin "ENABLE") (pinfunction "~{ENABLE}_ENABLE") (pintype "passive"))
    )
    (net (code "72") (name "/Y-MAX") (class "Default")
      (node (ref "C14") (pin "2") (pintype "passive"))
      (node (ref "P4") (pin "1") (pinfunction "1_1") (pintype "passive"))
      (node (ref "SHIELD1") (pin "RX3") (pinfunction "15(RX3)_RX3") (pintype "passive"))
    )
    (net (code "73") (name "/Y-MIN") (class "Default")
      (node (ref "C13") (pin "2") (pintype "passive"))
      (node (ref "P3") (pin "1") (pinfunction "1_1") (pintype "passive"))
      (node (ref "SHIELD1") (pin "TX3") (pinfunction "14(TX3)_TX3") (pintype "passive"))
    )
    (net (code "74") (name "/Y-STEP") (class "Default")
      (node (ref "SHIELD1") (pin "A6") (pinfunction "A6_A6") (pintype "passive"))
      (node (ref "Y") (pin "STEP") (pinfunction "STEP_STEP") (pintype "passive"))
    )
    (net (code "75") (name "/Z-DIR") (class "Default")
      (node (ref "SHIELD1") (pin "48") (pinfunction "48_48") (pintype "passive"))
      (node (ref "Z") (pin "DIR") (pinfunction "DIR_DIR") (pintype "passive"))
    )
    (net (code "76") (name "/Z-EN") (class "Default")
      (node (ref "R15") (pin "1") (pinfunction "1_1") (pintype "passive"))
      (node (ref "SHIELD1") (pin "A8") (pinfunction "A8_A8") (pintype "passive"))
      (node (ref "Z") (pin "ENABLE") (pinfunction "~{ENABLE}_ENABLE") (pintype "passive"))
    )
    (net (code "77") (name "/Z-MAX") (class "Default")
      (node (ref "C16") (pin "2") (pintype "passive"))
      (node (ref "P6") (pin "1") (pinfunction "1_1") (pintype "passive"))
      (node (ref "SHIELD1") (pin "RX1") (pinfunction "19(RX1)_RX1") (pintype "passive"))
    )
    (net (code "78") (name "/Z-MIN") (class "Default")
      (node (ref "C15") (pin "2") (pintype "passive"))
      (node (ref "P5") (pin "1") (pinfunction "1_1") (pintype "passive"))
      (node (ref "SHIELD1") (pin "TX1") (pinfunction "18(TX1)_TX1") (pintype "passive"))
    )
    (net (code "79") (name "/Z-STEP") (class "Default")
      (node (ref "SHIELD1") (pin "46") (pinfunction "46_46") (pintype "passive"))
      (node (ref "Z") (pin "STEP") (pinfunction "STEP_STEP") (pintype "passive"))
    )
    (net (code "80") (name "3.3V") (class "Default")
      (node (ref "SHIELD1") (pin "3V3") (pinfunction "3.3V_3V3") (pintype "passive"))
    )
    (net (code "81") (name "5V") (class "Default")
      (node (ref "P24") (pin "1") (pinfunction "1_1") (pintype "passive"))
      (node (ref "P25") (pin "1") (pinfunction "1_1") (pintype "passive"))
      (node (ref "P26") (pin "1") (pinfunction "1_1") (pintype "passive"))
      (node (ref "P27") (pin "1") (pinfunction "1_1") (pintype "passive"))
      (node (ref "P28") (pin "18") (pinfunction "18_18") (pintype "passive"))
      (node (ref "P29") (pin "1") (pinfunction "1_1") (pintype "passive"))
      (node (ref "P8") (pin "1") (pinfunction "1_1") (pintype "passive"))
      (node (ref "SHIELD1") (pin "5V") (pinfunction "5V_5V") (pintype "passive"))
    )
    (net (code "82") (name "AREF") (class "Default")
      (node (ref "SHIELD1") (pin "AREF") (pinfunction "AREF_AREF") (pintype "passive"))
    )
    (net (code "83") (name "GND") (class "Default")
      (node (ref "C1") (pin "-") (pintype "passive"))
      (node (ref "C10") (pin "2") (pinfunction "2_2") (pintype "passive"))
      (node (ref "C11") (pin "1") (pintype "passive"))
      (node (ref "C12") (pin "1") (pintype "passive"))
      (node (ref "C13") (pin "1") (pintype "passive"))
      (node (ref "C14") (pin "1") (pintype "passive"))
      (node (ref "C15") (pin "1") (pintype "passive"))
      (node (ref "C16") (pin "1") (pintype "passive"))
      (node (ref "C2") (pin "2") (pintype "passive"))
      (node (ref "C3") (pin "2") (pinfunction "2_2") (pintype "passive"))
      (node (ref "C4") (pin "2") (pinfunction "2_2") (pintype "passive"))
      (node (ref "C5") (pin "-") (pintype "passive"))
      (node (ref "C6") (pin "2") (pinfunction "2_2") (pintype "passive"))
      (node (ref "C7") (pin "2") (pinfunction "2_2") (pintype "passive"))
      (node (ref "C8") (pin "-") (pintype "passive"))
      (node (ref "C9") (pin "2") (pinfunction "2_2") (pintype "passive"))
      (node (ref "D2") (pin "A") (pinfunction "A_A") (pintype "passive"))
      (node (ref "E0") (pin "GND") (pinfunction "GND_GND") (pintype "passive"))
      (node (ref "E0") (pin "GND2") (pinfunction "GND_GND2") (pintype "passive"))
      (node (ref "E1") (pin "GND") (pinfunction "GND_GND") (pintype "passive"))
      (node (ref "E1") (pin "GND2") (pinfunction "GND_GND2") (pintype "passive"))
      (node (ref "LED1") (pin "C") (pinfunction "C_C") (pintype "passive"))
      (node (ref "P1") (pin "2") (pinfunction "2_2") (pintype "passive"))
      (node (ref "P10") (pin "1") (pinfunction "1_1") (pintype "passive"))
      (node (ref "P11") (pin "1") (pinfunction "1_1") (pintype "passive"))
      (node (ref "P12") (pin "1") (pinfunction "1_1") (pintype "passive"))
      (node (ref "P19") (pin "2") (pinfunction "2_2") (pintype "passive"))
      (node (ref "P2") (pin "2") (pinfunction "2_2") (pintype "passive"))
      (node (ref "P24") (pin "2") (pinfunction "2_2") (pintype "passive"))
      (node (ref "P26") (pin "2") (pinfunction "2_2") (pintype "passive"))
      (node (ref "P27") (pin "7") (pinfunction "7_7") (pintype "passive"))
      (node (ref "P28") (pin "17") (pinfunction "17_17") (pintype "passive"))
      (node (ref "P29") (pin "2") (pinfunction "2_2") (pintype "passive"))
      (node (ref "P3") (pin "2") (pinfunction "2_2") (pintype "passive"))
      (node (ref "P30") (pin "2") (pinfunction "2_2") (pintype "passive"))
      (node (ref "P4") (pin "2") (pinfunction "2_2") (pintype "passive"))
      (node (ref "P5") (pin "2") (pinfunction "2_2") (pintype "passive"))
      (node (ref "P6") (pin "2") (pinfunction "2_2") (pintype "passive"))
      (node (ref "P7") (pin "1") (pinfunction "1_1") (pintype "passive"))
      (node (ref "P7") (pin "3") (pinfunction "3_3") (pintype "passive"))
      (node (ref "P7") (pin "5") (pinfunction "5_5") (pintype "passive"))
      (node (ref "P9") (pin "1") (pinfunction "1_1") (pintype "passive"))
      (node (ref "Q1") (pin "S") (pinfunction "3_S") (pintype "passive"))
      (node (ref "Q2") (pin "S") (pinfunction "3_S") (pintype "passive"))
      (node (ref "Q3") (pin "S") (pinfunction "3_S") (pintype "passive"))
      (node (ref "Q4") (pin "1") (pinfunction "S_1") (pintype "passive"))
      (node (ref "Q4") (pin "3") (pinfunction "S_3") (pintype "passive"))
      (node (ref "R13") (pin "1") (pinfunction "1_1") (pintype "passive"))
      (node (ref "R4") (pin "1") (pinfunction "1_1") (pintype "passive"))
      (node (ref "R8") (pin "1") (pinfunction "1_1") (pintype "passive"))
      (node (ref "S1") (pin "1") (pintype "passive"))
      (node (ref "SHIELD1") (pin "GND") (pinfunction "GND_GND") (pintype "passive"))
      (node (ref "X") (pin "GND") (pinfunction "GND_GND") (pintype "passive"))
      (node (ref "X") (pin "GND2") (pinfunction "GND_GND2") (pintype "passive"))
      (node (ref "X1") (pin "2") (pinfunction "2_2") (pintype "passive"))
      (node (ref "X1") (pin "4") (pinfunction "4_4") (pintype "passive"))
      (node (ref "Y") (pin "GND") (pinfunction "GND_GND") (pintype "passive"))
      (node (ref "Y") (pin "GND2") (pinfunction "GND_GND2") (pintype "passive"))
      (node (ref "Z") (pin "GND") (pinfunction "GND_GND") (pintype "passive"))
      (node (ref "Z") (pin "GND2") (pinfunction "GND_GND2") (pintype "passive"))
    )
    (net (code "84") (name "IOREF") (class "Default")
      (node (ref "P8") (pin "3") (pinfunction "3_3") (pintype "passive"))
      (node (ref "SHIELD1") (pin "IOREF") (pinfunction "IOREF_IOREF") (pintype "passive"))
    )
    (net (code "85") (name "Net-(D1-PadK)") (class "Default")
      (node (ref "D1") (pin "K") (pinfunction "K_K") (pintype "passive"))
      (node (ref "P32") (pin "2") (pinfunction "2_2") (pintype "passive"))
    )
    (net (code "86") (name "Net-(E0-Pad1A)") (class "Default")
      (node (ref "E0") (pin "1A") (pinfunction "1A_1A") (pintype "passive"))
      (node (ref "P23") (pin "3") (pinfunction "3_3") (pintype "passive"))
    )
    (net (code "87") (name "Net-(E0-Pad1B)") (class "Default")
      (node (ref "E0") (pin "1B") (pinfunction "1B_1B") (pintype "passive"))
      (node (ref "P23") (pin "4") (pinfunction "4_4") (pintype "passive"))
    )
    (net (code "88") (name "Net-(E0-Pad2A)") (class "Default")
      (node (ref "E0") (pin "2A") (pinfunction "2A_2A") (pintype "passive"))
      (node (ref "P23") (pin "2") (pinfunction "2_2") (pintype "passive"))
    )
    (net (code "89") (name "Net-(E0-Pad2B)") (class "Default")
      (node (ref "E0") (pin "2B") (pinfunction "2B_2B") (pintype "passive"))
      (node (ref "P23") (pin "1") (pinfunction "1_1") (pintype "passive"))
    )
    (net (code "90") (name "Net-(E0-PadMS1)") (class "Default")
      (node (ref "E0") (pin "MS1") (pinfunction "MS1_MS1") (pintype "passive"))
      (node (ref "P21") (pin "1") (pinfunction "1_1") (pintype "passive"))
    )
    (net (code "91") (name "Net-(E0-PadMS2)") (class "Default")
      (node (ref "E0") (pin "MS2") (pinfunction "MS2_MS2") (pintype "passive"))
      (node (ref "P21") (pin "3") (pinfunction "3_3") (pintype "passive"))
    )
    (net (code "92") (name "Net-(E0-PadMS3)") (class "Default")
      (node (ref "E0") (pin "MS3") (pinfunction "MS3_MS3") (pintype "passive"))
      (node (ref "P21") (pin "5") (pinfunction "5_5") (pintype "passive"))
    )
    (net (code "93") (name "Net-(E0-~{RESET})") (class "Default")
      (node (ref "E0") (pin "RESET") (pinfunction "~{RESET}_RESET") (pintype "passive"))
      (node (ref "E0") (pin "SLEEP") (pinfunction "~{SLEEP}_SLEEP") (pintype "passive"))
    )
    (net (code "94") (name "Net-(E1-Pad1A)") (class "Default")
      (node (ref "E1") (pin "1A") (pinfunction "1A_1A") (pintype "passive"))
      (node (ref "P18") (pin "3") (pinfunction "3_3") (pintype "passive"))
    )
    (net (code "95") (name "Net-(E1-Pad1B)") (class "Default")
      (node (ref "E1") (pin "1B") (pinfunction "1B_1B") (pintype "passive"))
      (node (ref "P18") (pin "4") (pinfunction "4_4") (pintype "passive"))
    )
    (net (code "96") (name "Net-(E1-Pad2A)") (class "Default")
      (node (ref "E1") (pin "2A") (pinfunction "2A_2A") (pintype "passive"))
      (node (ref "P18") (pin "2") (pinfunction "2_2") (pintype "passive"))
    )
    (net (code "97") (name "Net-(E1-Pad2B)") (class "Default")
      (node (ref "E1") (pin "2B") (pinfunction "2B_2B") (pintype "passive"))
      (node (ref "P18") (pin "1") (pinfunction "1_1") (pintype "passive"))
    )
    (net (code "98") (name "Net-(E1-PadMS1)") (class "Default")
      (node (ref "E1") (pin "MS1") (pinfunction "MS1_MS1") (pintype "passive"))
      (node (ref "P15") (pin "1") (pinfunction "1_1") (pintype "passive"))
    )
    (net (code "99") (name "Net-(E1-PadMS2)") (class "Default")
      (node (ref "E1") (pin "MS2") (pinfunction "MS2_MS2") (pintype "passive"))
      (node (ref "P15") (pin "3") (pinfunction "3_3") (pintype "passive"))
    )
    (net (code "100") (name "Net-(E1-PadMS3)") (class "Default")
      (node (ref "E1") (pin "MS3") (pinfunction "MS3_MS3") (pintype "passive"))
      (node (ref "P15") (pin "5") (pinfunction "5_5") (pintype "passive"))
    )
    (net (code "101") (name "Net-(E1-~{RESET})") (class "Default")
      (node (ref "E1") (pin "RESET") (pinfunction "~{RESET}_RESET") (pintype "passive"))
      (node (ref "E1") (pin "SLEEP") (pinfunction "~{SLEEP}_SLEEP") (pintype "passive"))
    )
    (net (code "102") (name "Net-(F1-Pad1)") (class "Default")
      (node (ref "F1") (pin "1") (pinfunction "1_1") (pintype "passive"))
      (node (ref "X1") (pin "3") (pinfunction "3_3") (pintype "passive"))
    )
    (net (code "103") (name "Net-(F2-Pad1)") (class "Default")
      (node (ref "F2") (pin "1") (pinfunction "1_1") (pintype "passive"))
      (node (ref "X1") (pin "1") (pinfunction "1_1") (pintype "passive"))
    )
    (net (code "104") (name "Net-(LED1-PadA)") (class "Default")
      (node (ref "LED1") (pin "A") (pinfunction "A_A") (pintype "passive"))
      (node (ref "R12") (pin "2") (pinfunction "2_2") (pintype "passive"))
    )
    (net (code "105") (name "Net-(LED2-PadA)") (class "Default")
      (node (ref "LED2") (pin "A") (pinfunction "A_A") (pintype "passive"))
      (node (ref "R10") (pin "2") (pinfunction "2_2") (pintype "passive"))
    )
    (net (code "106") (name "Net-(LED3-PadA)") (class "Default")
      (node (ref "LED3") (pin "A") (pinfunction "A_A") (pintype "passive"))
      (node (ref "R6") (pin "2") (pinfunction "2_2") (pintype "passive"))
    )
    (net (code "107") (name "Net-(LED4-PadA)") (class "Default")
      (node (ref "LED4") (pin "A") (pinfunction "A_A") (pintype "passive"))
      (node (ref "R3") (pin "2") (pinfunction "2_2") (pintype "passive"))
    )
    (net (code "108") (name "Net-(LED5-PadA)") (class "Default")
      (node (ref "LED5") (pin "A") (pinfunction "A_A") (pintype "passive"))
      (node (ref "R20") (pin "2") (pinfunction "2_2") (pintype "passive"))
    )
    (net (code "109") (name "Net-(LED6-PadA)") (class "Default")
      (node (ref "LED6") (pin "A") (pinfunction "A_A") (pintype "passive"))
      (node (ref "R19") (pin "2") (pinfunction "2_2") (pintype "passive"))
    )
    (net (code "110") (name "Net-(P13-Pad1)") (class "Default")
      (node (ref "P13") (pin "1") (pinfunction "1_1") (pintype "passive"))
      (node (ref "X") (pin "MS1") (pinfunction "MS1_MS1") (pintype "passive"))
    )
    (net (code "111") (name "Net-(P13-Pad3)") (class "Default")
      (node (ref "P13") (pin "3") (pinfunction "3_3") (pintype "passive"))
      (node (ref "X") (pin "MS2") (pinfunction "MS2_MS2") (pintype "passive"))
    )
    (net (code "112") (name "Net-(P13-Pad5)") (class "Default")
      (node (ref "P13") (pin "5") (pinfunction "5_5") (pintype "passive"))
      (node (ref "X") (pin "MS3") (pinfunction "MS3_MS3") (pintype "passive"))
    )
    (net (code "113") (name "Net-(P14-Pad1)") (class "Default")
      (node (ref "P14") (pin "1") (pinfunction "1_1") (pintype "passive"))
      (node (ref "Z") (pin "MS1") (pinfunction "MS1_MS1") (pintype "passive"))
    )
    (net (code "114") (name "Net-(P14-Pad3)") (class "Default")
      (node (ref "P14") (pin "3") (pinfunction "3_3") (pintype "passive"))
      (node (ref "Z") (pin "MS2") (pinfunction "MS2_MS2") (pintype "passive"))
    )
    (net (code "115") (name "Net-(P14-Pad5)") (class "Default")
      (node (ref "P14") (pin "5") (pinfunction "5_5") (pintype "passive"))
      (node (ref "Z") (pin "MS3") (pinfunction "MS3_MS3") (pintype "passive"))
    )
    (net (code "116") (name "Net-(P16-Pad1)") (class "Default")
      (node (ref "P16") (pin "1") (pinfunction "1_1") (pintype "passive"))
      (node (ref "X") (pin "2B") (pinfunction "2B_2B") (pintype "passive"))
    )
    (net (code "117") (name "Net-(P16-Pad2)") (class "Default")
      (node (ref "P16") (pin "2") (pinfunction "2_2") (pintype "passive"))
      (node (ref "X") (pin "2A") (pinfunction "2A_2A") (pintype "passive"))
    )
    (net (code "118") (name "Net-(P16-Pad3)") (class "Default")
      (node (ref "P16") (pin "3") (pinfunction "3_3") (pintype "passive"))
      (node (ref "X") (pin "1A") (pinfunction "1A_1A") (pintype "passive"))
    )
    (net (code "119") (name "Net-(P16-Pad4)") (class "Default")
      (node (ref "P16") (pin "4") (pinfunction "4_4") (pintype "passive"))
      (node (ref "X") (pin "1B") (pinfunction "1B_1B") (pintype "passive"))
    )
    (net (code "120") (name "Net-(P17-Pad1)") (class "Default")
      (node (ref "P17") (pin "1") (pinfunction "1_1") (pintype "passive"))
      (node (ref "P17") (pin "2") (pinfunction "2_2") (pintype "passive"))
      (node (ref "Z") (pin "2B") (pinfunction "2B_2B") (pintype "passive"))
    )
    (net (code "121") (name "Net-(P17-Pad3)") (class "Default")
      (node (ref "P17") (pin "3") (pinfunction "3_3") (pintype "passive"))
      (node (ref "P17") (pin "4") (pinfunction "4_4") (pintype "passive"))
      (node (ref "Z") (pin "2A") (pinfunction "2A_2A") (pintype "passive"))
    )
    (net (code "122") (name "Net-(P17-Pad5)") (class "Default")
      (node (ref "P17") (pin "5") (pinfunction "5_5") (pintype "passive"))
      (node (ref "P17") (pin "6") (pinfunction "6_6") (pintype "passive"))
      (node (ref "Z") (pin "1A") (pinfunction "1A_1A") (pintype "passive"))
    )
    (net (code "123") (name "Net-(P17-Pad7)") (class "Default")
      (node (ref "P17") (pin "7") (pinfunction "7_7") (pintype "passive"))
      (node (ref "P17") (pin "8") (pinfunction "8_8") (pintype "passive"))
      (node (ref "Z") (pin "1B") (pinfunction "1B_1B") (pintype "passive"))
    )
    (net (code "124") (name "Net-(P20-Pad1)") (class "Default")
      (node (ref "P20") (pin "1") (pinfunction "1_1") (pintype "passive"))
      (node (ref "Y") (pin "MS1") (pinfunction "MS1_MS1") (pintype "passive"))
    )
    (net (code "125") (name "Net-(P20-Pad3)") (class "Default")
      (node (ref "P20") (pin "3") (pinfunction "3_3") (pintype "passive"))
      (node (ref "Y") (pin "MS2") (pinfunction "MS2_MS2") (pintype "passive"))
    )
    (net (code "126") (name "Net-(P20-Pad5)") (class "Default")
      (node (ref "P20") (pin "5") (pinfunction "5_5") (pintype "passive"))
      (node (ref "Y") (pin "MS3") (pinfunction "MS3_MS3") (pintype "passive"))
    )
    (net (code "127") (name "Net-(P22-Pad1)") (class "Default")
      (node (ref "P22") (pin "1") (pinfunction "1_1") (pintype "passive"))
      (node (ref "Y") (pin "2B") (pinfunction "2B_2B") (pintype "passive"))
    )
    (net (code "128") (name "Net-(P22-Pad2)") (class "Default")
      (node (ref "P22") (pin "2") (pinfunction "2_2") (pintype "passive"))
      (node (ref "Y") (pin "2A") (pinfunction "2A_2A") (pintype "passive"))
    )
    (net (code "129") (name "Net-(P22-Pad3)") (class "Default")
      (node (ref "P22") (pin "3") (pinfunction "3_3") (pintype "passive"))
      (node (ref "Y") (pin "1A") (pinfunction "1A_1A") (pintype "passive"))
    )
    (net (code "130") (name "Net-(P22-Pad4)") (class "Default")
      (node (ref "P22") (pin "4") (pinfunction "4_4") (pintype "passive"))
      (node (ref "Y") (pin "1B") (pinfunction "1B_1B") (pintype "passive"))
    )
    (net (code "131") (name "Net-(Q1-PadG)") (class "Default")
      (node (ref "Q1") (pin "G") (pinfunction "G_G") (pintype "passive"))
      (node (ref "R2") (pin "1") (pinfunction "1_1") (pintype "passive"))
    )
    (net (code "132") (name "Net-(Q2-PadG)") (class "Default")
      (node (ref "Q2") (pin "G") (pinfunction "G_G") (pintype "passive"))
      (node (ref "R5") (pin "1") (pinfunction "1_1") (pintype "passive"))
    )
    (net (code "133") (name "Net-(Q3-PadG)") (class "Default")
      (node (ref "Q3") (pin "G") (pinfunction "G_G") (pintype "passive"))
      (node (ref "R9") (pin "1") (pinfunction "1_1") (pintype "passive"))
    )
    (net (code "134") (name "Net-(X-~{RESET})") (class "Default")
      (node (ref "X") (pin "RESET") (pinfunction "~{RESET}_RESET") (pintype "passive"))
      (node (ref "X") (pin "SLEEP") (pinfunction "~{SLEEP}_SLEEP") (pintype "passive"))
    )
    (net (code "135") (name "Net-(Y-~{RESET})") (class "Default")
      (node (ref "Y") (pin "RESET") (pinfunction "~{RESET}_RESET") (pintype "passive"))
      (node (ref "Y") (pin "SLEEP") (pinfunction "~{SLEEP}_SLEEP") (pintype "passive"))
    )
    (net (code "136") (name "Net-(Z-~{RESET})") (class "Default")
      (node (ref "Z") (pin "RESET") (pinfunction "~{RESET}_RESET") (pintype "passive"))
      (node (ref "Z") (pin "SLEEP") (pinfunction "~{SLEEP}_SLEEP") (pintype "passive"))
    )
    (net (code "137") (name "SERVO_5V") (class "Default")
      (node (ref "P10") (pin "2") (pinfunction "2_2") (pintype "passive"))
      (node (ref "P11") (pin "2") (pinfunction "2_2") (pintype "passive"))
      (node (ref "P12") (pin "2") (pinfunction "2_2") (pintype "passive"))
      (node (ref "P25") (pin "2") (pinfunction "2_2") (pintype "passive"))
      (node (ref "P9") (pin "2") (pinfunction "2_2") (pintype "passive"))
    )
    (net (code "138") (name "V_LOGIC") (class "Default")
      (node (ref "E0") (pin "Vdd") (pinfunction "VDD_Vdd") (pintype "passive"))
      (node (ref "E1") (pin "Vdd") (pinfunction "VDD_Vdd") (pintype "passive"))
      (node (ref "P1") (pin "3") (pinfunction "3_3") (pintype "passive"))
      (node (ref "P13") (pin "2") (pinfunction "2_2") (pintype "passive"))
      (node (ref "P13") (pin "4") (pinfunction "4_4") (pintype "passive"))
      (node (ref "P13") (pin "6") (pinfunction "6_6") (pintype "passive"))
      (node (ref "P14") (pin "2") (pinfunction "2_2") (pintype "passive"))
      (node (ref "P14") (pin "4") (pinfunction "4_4") (pintype "passive"))
      (node (ref "P14") (pin "6") (pinfunction "6_6") (pintype "passive"))
      (node (ref "P15") (pin "2") (pinfunction "2_2") (pintype "passive"))
      (node (ref "P15") (pin "4") (pinfunction "4_4") (pintype "passive"))
      (node (ref "P15") (pin "6") (pinfunction "6_6") (pintype "passive"))
      (node (ref "P19") (pin "1") (pinfunction "1_1") (pintype "passive"))
      (node (ref "P2") (pin "3") (pinfunction "3_3") (pintype "passive"))
      (node (ref "P20") (pin "2") (pinfunction "2_2") (pintype "passive"))
      (node (ref "P20") (pin "4") (pinfunction "4_4") (pintype "passive"))
      (node (ref "P20") (pin "6") (pinfunction "6_6") (pintype "passive"))
      (node (ref "P21") (pin "2") (pinfunction "2_2") (pintype "passive"))
      (node (ref "P21") (pin "4") (pinfunction "4_4") (pintype "passive"))
      (node (ref "P21") (pin "6") (pinfunction "6_6") (pintype "passive"))
      (node (ref "P3") (pin "3") (pinfunction "3_3") (pintype "passive"))
      (node (ref "P4") (pin "3") (pinfunction "3_3") (pintype "passive"))
      (node (ref "P5") (pin "3") (pinfunction "3_3") (pintype "passive"))
      (node (ref "P6") (pin "3") (pinfunction "3_3") (pintype "passive"))
      (node (ref "P8") (pin "2") (pinfunction "2_2") (pintype "passive"))
      (node (ref "R1") (pin "1") (pinfunction "1_1") (pintype "passive"))
      (node (ref "R11") (pin "1") (pinfunction "1_1") (pintype "passive"))
      (node (ref "R14") (pin "2") (pinfunction "2_2") (pintype "passive"))
      (node (ref "R15") (pin "2") (pinfunction "2_2") (pintype "passive"))
      (node (ref "R16") (pin "2") (pinfunction "2_2") (pintype "passive"))
      (node (ref "R17") (pin "2") (pinfunction "2_2") (pintype "passive"))
      (node (ref "R18") (pin "2") (pinfunction "2_2") (pintype "passive"))
      (node (ref "R21") (pin "1") (pinfunction "1_1") (pintype "passive"))
      (node (ref "R22") (pin "1") (pinfunction "1_1") (pintype "passive"))
      (node (ref "R7") (pin "1") (pinfunction "1_1") (pintype "passive"))
      (node (ref "X") (pin "Vdd") (pinfunction "VDD_Vdd") (pintype "passive"))
      (node (ref "Y") (pin "Vdd") (pinfunction "VDD_Vdd") (pintype "passive"))
      (node (ref "Z") (pin "Vdd") (pinfunction "VDD_Vdd") (pintype "passive"))
    )
    (net (code "139") (name "unconnected-(P27-Pad8)") (class "Default")
      (node (ref "P27") (pin "8") (pinfunction "8_8") (pintype "passive"))
    )
  )
)
